# proy_10B_SCH_2_v1i1.net
KiCad netlist of a schematic drawn in Altium Designer
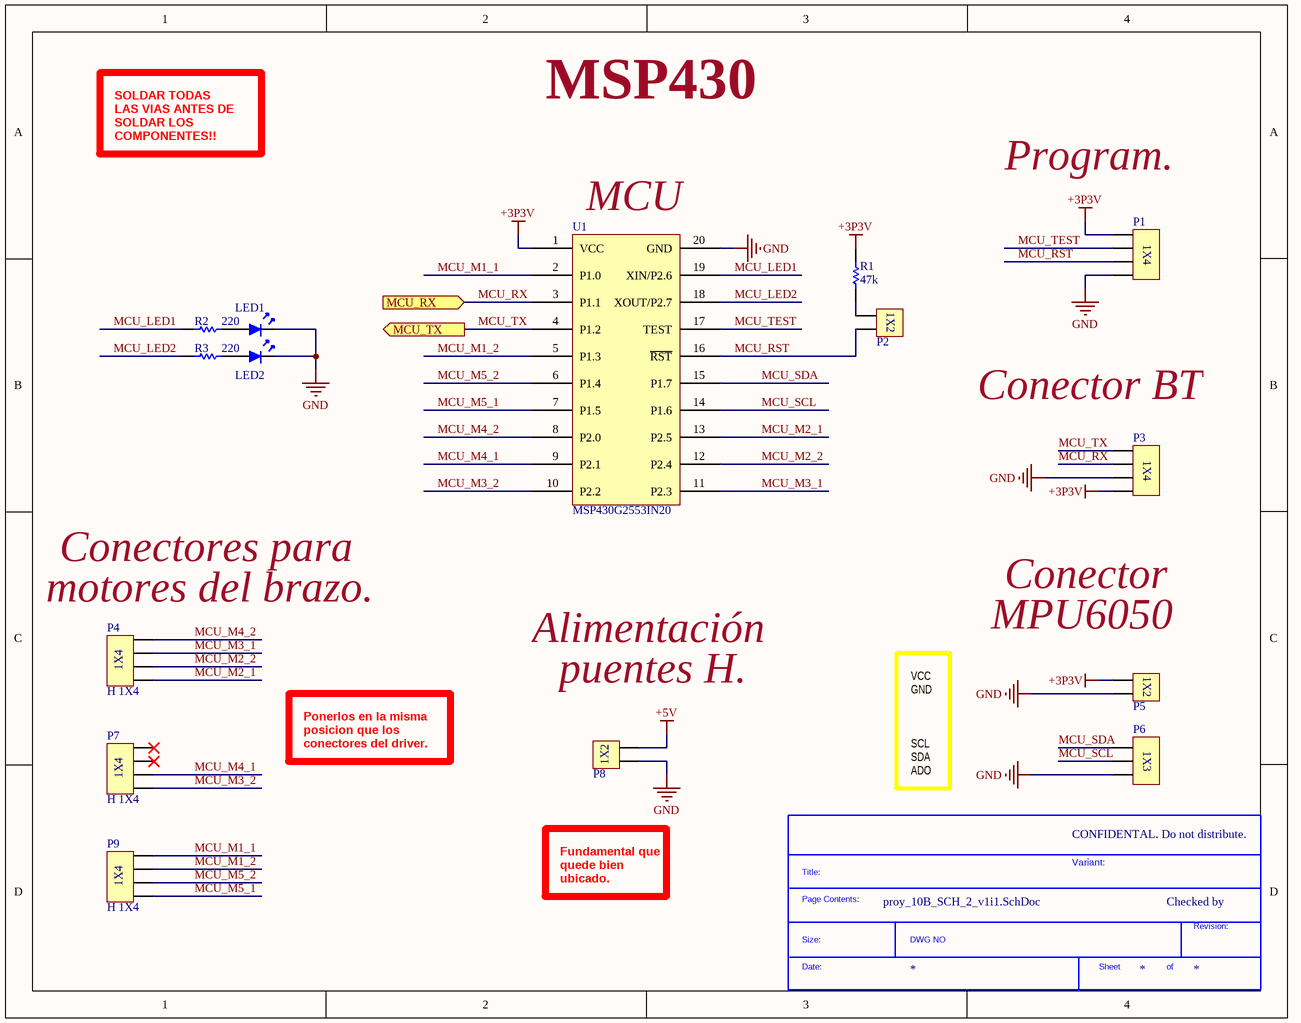
[diagram p0: proy_10B_SCH_2_v1i1.SchDoc]

(export (version "E")
  (design (tool "Eeschema 10.0.6"))
  (components
    (comp (ref "*") (value "SDTitleBlock") (libsource (lib "*") (part "SDTitleBlock")))
    (comp (ref "LED1")
      (value "LED")
      (footprint "LED 1206")
      (fields (field (name ".CREATOR") "SR"))
      (libsource (lib "Libreria_Santi") (part "LED"))
    )
    (comp (ref "LED2")
      (value "LED")
      (footprint "LED 1206")
      (fields (field (name ".CREATOR") "SR"))
      (libsource (lib "Libreria_Santi") (part "LED"))
    )
    (comp (ref "P1")
      (value "H 1X4")
      (footprint "H 1X4")
      (description "PIN HEADER 1X4")
      (fields (field (name ".CREATOR") "SR"))
      (libsource (lib "") (part "H 1X4_1"))
    )
    (comp (ref "P2")
      (value "H 1X2")
      (footprint "H 1x2")
      (description "PIN HEADER 1X2")
      (fields (field (name ".CREATOR") "SR"))
      (libsource (lib "") (part "H 1X2_1"))
    )
    (comp (ref "P3")
      (value "H 1X4")
      (footprint "H 1X4 - Hembra")
      (description "PIN HEADER 1X4")
      (fields (field (name ".CREATOR") "SR"))
      (libsource (lib "") (part "H 1X4_1"))
    )
    (comp (ref "P4")
      (value "H 1X4")
      (footprint "H 1X4")
      (description "PIN HEADER 1X4")
      (fields (field (name ".CREATOR") "SR"))
      (libsource (lib "Libreria_Santi") (part "H 1X4"))
    )
    (comp (ref "P5")
      (value "H 1X2")
      (footprint "H 1x2")
      (description "PIN HEADER 1X2")
      (fields (field (name ".CREATOR") "SR"))
      (libsource (lib "") (part "H 1X2_1"))
    )
    (comp (ref "P6")
      (value "H 1X3")
      (footprint "H 1x3")
      (description "PIN HEADER 1X3")
      (fields (field (name ".CREATOR") "SR"))
      (libsource (lib "Libreria_Santi") (part "H 1X3"))
    )
    (comp (ref "P7")
      (value "H 1X4")
      (footprint "H 1X4")
      (description "PIN HEADER 1X4")
      (fields (field (name ".CREATOR") "SR"))
      (libsource (lib "Libreria_Santi") (part "H 1X4"))
    )
    (comp (ref "P8")
      (value "H 1X2")
      (footprint "H 1x2 - Hembra")
      (description "PIN HEADER 1X2")
      (fields (field (name ".CREATOR") "SR"))
      (libsource (lib "Libreria_Santi") (part "H 1X2"))
    )
    (comp (ref "P9")
      (value "H 1X4")
      (footprint "H 1X4")
      (description "PIN HEADER 1X4")
      (fields (field (name ".CREATOR") "SR"))
      (libsource (lib "Libreria_Santi") (part "H 1X4"))
    )
    (comp (ref "R1")
      (value "47k")
      (footprint "R 1206")
      (description "Resistencia")
      (fields (field (name ".CREATOR") "SR"))
      (libsource (lib "Libreria_Santi") (part "R"))
    )
    (comp (ref "R2")
      (value "220")
      (footprint "R 1206")
      (description "Resistencia")
      (fields (field (name ".CREATOR") "SR"))
      (libsource (lib "Libreria_Santi") (part "R"))
    )
    (comp (ref "R3")
      (value "220")
      (footprint "R 1206")
      (description "Resistencia")
      (fields (field (name ".CREATOR") "SR"))
      (libsource (lib "Libreria_Santi") (part "R"))
    )
    (comp (ref "U1")
      (value "MSP430G2553IN20")
      (footprint "PW-20")
      (description "IC MCU 16BIT 16KB FLASH 20PDIP")
      (fields
        (field (name "MANUFACTURER") "Texas Instruments")
        (field (name ".CREATOR") "SR")
        (field (name ".PCBCHECK") "SR")
        (field (name ".SCHCHECK") "SR")
      )
      (libsource (lib "Libreria_Santi") (part "MSP430G2553IN20"))
    )
  )
  (nets
    (net (code "1") (name "+3P3V") (class "Default")
      (node (ref "P1") (pin "1") (pinfunction "1_1") (pintype "passive"))
      (node (ref "P3") (pin "4") (pinfunction "4_4") (pintype "passive"))
      (node (ref "P5") (pin "1") (pinfunction "1_1") (pintype "passive"))
      (node (ref "R1") (pin "2") (pinfunction "2_2") (pintype "passive"))
      (node (ref "U1") (pin "1") (pinfunction "VCC_1") (pintype "passive"))
    )
    (net (code "2") (name "+5V") (class "Default")
      (node (ref "P8") (pin "2") (pinfunction "2_2") (pintype "passive"))
    )
    (net (code "3") (name "/MCU_LED1") (class "Default")
      (node (ref "R2") (pin "1") (pinfunction "1_1") (pintype "passive"))
      (node (ref "U1") (pin "19") (pinfunction "XIN/P2.6_19") (pintype "passive"))
    )
    (net (code "4") (name "/MCU_LED2") (class "Default")
      (node (ref "R3") (pin "1") (pinfunction "1_1") (pintype "passive"))
      (node (ref "U1") (pin "18") (pinfunction "XOUT/P2.7_18") (pintype "passive"))
    )
    (net (code "5") (name "/MCU_M1_1") (class "Default")
      (node (ref "P9") (pin "4") (pinfunction "4_4") (pintype "passive"))
      (node (ref "U1") (pin "2") (pinfunction "P1.0_2") (pintype "passive"))
    )
    (net (code "6") (name "/MCU_M1_2") (class "Default")
      (node (ref "P9") (pin "3") (pinfunction "3_3") (pintype "passive"))
      (node (ref "U1") (pin "5") (pinfunction "P1.3_5") (pintype "passive"))
    )
    (net (code "7") (name "/MCU_M2_1") (class "Default")
      (node (ref "P4") (pin "1") (pinfunction "1_1") (pintype "passive"))
      (node (ref "U1") (pin "13") (pinfunction "P2.5_13") (pintype "passive"))
    )
    (net (code "8") (name "/MCU_M2_2") (class "Default")
      (node (ref "P4") (pin "2") (pinfunction "2_2") (pintype "passive"))
      (node (ref "U1") (pin "12") (pinfunction "P2.4_12") (pintype "passive"))
    )
    (net (code "9") (name "/MCU_M3_1") (class "Default")
      (node (ref "P4") (pin "3") (pinfunction "3_3") (pintype "passive"))
      (node (ref "U1") (pin "11") (pinfunction "P2.3_11") (pintype "passive"))
    )
    (net (code "10") (name "/MCU_M3_2") (class "Default")
      (node (ref "P7") (pin "1") (pinfunction "1_1") (pintype "passive"))
      (node (ref "U1") (pin "10") (pinfunction "P2.2_10") (pintype "passive"))
    )
    (net (code "11") (name "/MCU_M4_1") (class "Default")
      (node (ref "P7") (pin "2") (pinfunction "2_2") (pintype "passive"))
      (node (ref "U1") (pin "9") (pinfunction "P2.1_9") (pintype "passive"))
    )
    (net (code "12") (name "/MCU_M4_2") (class "Default")
      (node (ref "P4") (pin "4") (pinfunction "4_4") (pintype "passive"))
      (node (ref "U1") (pin "8") (pinfunction "P2.0_8") (pintype "passive"))
    )
    (net (code "13") (name "/MCU_M5_1") (class "Default")
      (node (ref "P9") (pin "1") (pinfunction "1_1") (pintype "passive"))
      (node (ref "U1") (pin "7") (pinfunction "P1.5_7") (pintype "passive"))
    )
    (net (code "14") (name "/MCU_M5_2") (class "Default")
      (node (ref "P9") (pin "2") (pinfunction "2_2") (pintype "passive"))
      (node (ref "U1") (pin "6") (pinfunction "P1.4_6") (pintype "passive"))
    )
    (net (code "15") (name "/MCU_RST") (class "Default")
      (node (ref "P1") (pin "3") (pinfunction "3_3") (pintype "passive"))
      (node (ref "P2") (pin "2") (pinfunction "2_2") (pintype "passive"))
      (node (ref "U1") (pin "16") (pinfunction "~{RST}_16") (pintype "passive"))
    )
    (net (code "16") (name "/MCU_RX") (class "Default")
      (node (ref "P3") (pin "2") (pinfunction "2_2") (pintype "passive"))
      (node (ref "U1") (pin "3") (pinfunction "P1.1_3") (pintype "passive"))
    )
    (net (code "17") (name "/MCU_SCL") (class "Default")
      (node (ref "P6") (pin "2") (pinfunction "2_2") (pintype "passive"))
      (node (ref "U1") (pin "14") (pinfunction "P1.6_14") (pintype "passive"))
    )
    (net (code "18") (name "/MCU_SDA") (class "Default")
      (node (ref "P6") (pin "1") (pinfunction "1_1") (pintype "passive"))
      (node (ref "U1") (pin "15") (pinfunction "P1.7_15") (pintype "passive"))
    )
    (net (code "19") (name "/MCU_TEST") (class "Default")
      (node (ref "P1") (pin "2") (pinfunction "2_2") (pintype "passive"))
      (node (ref "U1") (pin "17") (pinfunction "TEST_17") (pintype "passive"))
    )
    (net (code "20") (name "/MCU_TX") (class "Default")
      (node (ref "P3") (pin "1") (pinfunction "1_1") (pintype "passive"))
      (node (ref "U1") (pin "4") (pinfunction "P1.2_4") (pintype "passive"))
    )
    (net (code "21") (name "GND") (class "Default")
      (node (ref "LED1") (pin "2") (pinfunction "K_2") (pintype "passive"))
      (node (ref "LED2") (pin "2") (pinfunction "K_2") (pintype "passive"))
      (node (ref "P1") (pin "4") (pinfunction "4_4") (pintype "passive"))
      (node (ref "P3") (pin "3") (pinfunction "3_3") (pintype "passive"))
      (node (ref "P5") (pin "2") (pinfunction "2_2") (pintype "passive"))
      (node (ref "P6") (pin "3") (pinfunction "3_3") (pintype "passive"))
      (node (ref "P8") (pin "1") (pinfunction "1_1") (pintype "passive"))
      (node (ref "U1") (pin "20") (pinfunction "GND_20") (pintype "passive"))
    )
    (net (code "22") (name "Net-(LED1-A)") (class "Default")
      (node (ref "LED1") (pin "1") (pinfunction "A_1") (pintype "passive"))
      (node (ref "R2") (pin "2") (pinfunction "2_2") (pintype "passive"))
    )
    (net (code "23") (name "Net-(LED2-A)") (class "Default")
      (node (ref "LED2") (pin "1") (pinfunction "A_1") (pintype "passive"))
      (node (ref "R3") (pin "2") (pinfunction "2_2") (pintype "passive"))
    )
    (net (code "24") (name "Net-(P2-Pad1)") (class "Default")
      (node (ref "P2") (pin "1") (pinfunction "1_1") (pintype "passive"))
      (node (ref "R1") (pin "1") (pinfunction "1_1") (pintype "passive"))
    )
    (net (code "25") (name "unconnected-(P7-Pad3)") (class "Default")
      (node (ref "P7") (pin "3") (pinfunction "3_3") (pintype "passive+no_connect"))
    )
    (net (code "26") (name "unconnected-(P7-Pad4)") (class "Default")
      (node (ref "P7") (pin "4") (pinfunction "4_4") (pintype "passive+no_connect"))
    )
  )
)
